# Obstacle_Avoider.net
KiCad netlist of a schematic drawn in EAGLE
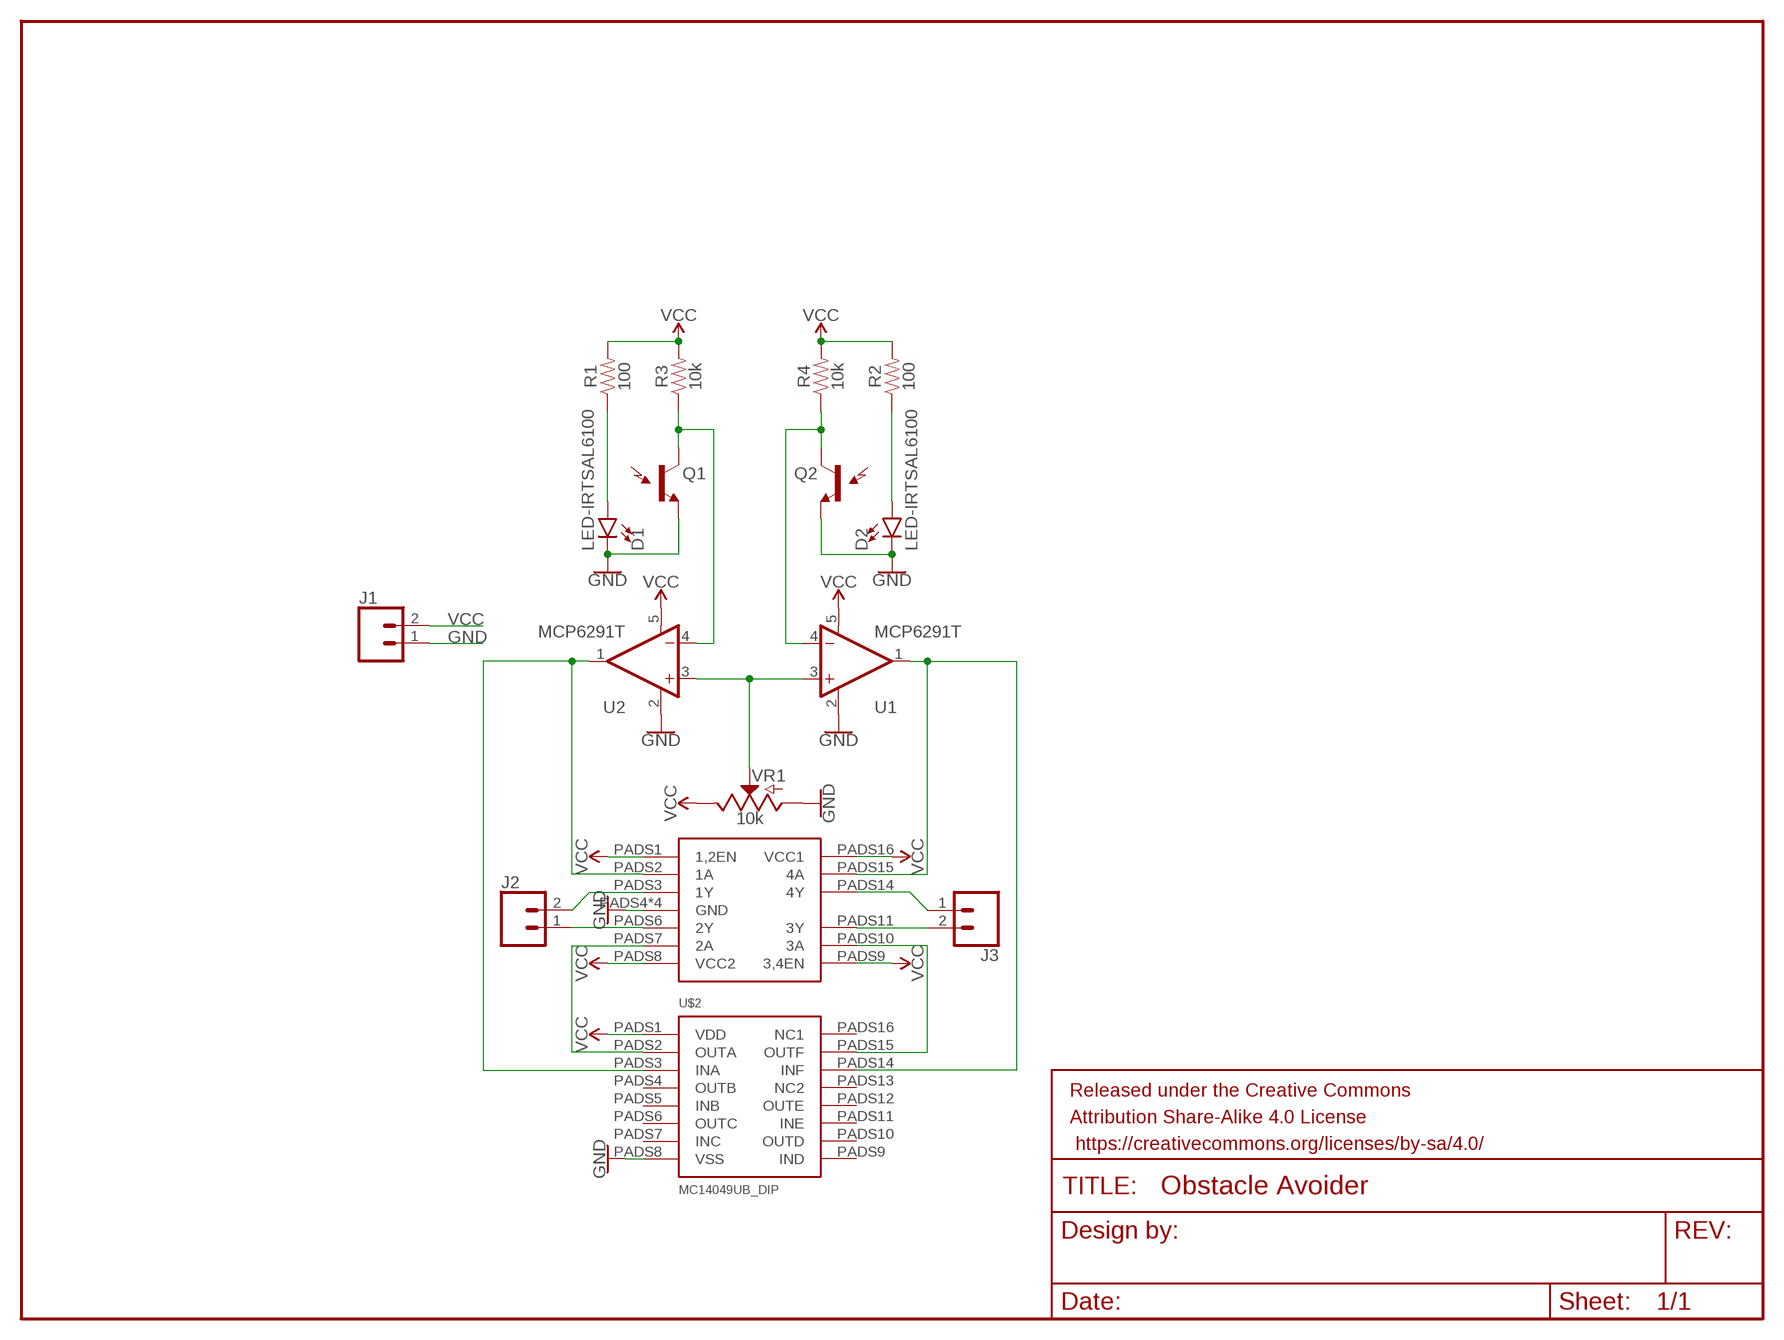
[diagram p0: schematic, sheet 1]

(export (version "E")
  (design (tool "Eeschema 10.0.6"))
  (components
    (comp (ref "D1")
      (value "LED-IRTSAL6100")
      (footprint "eagle-import:LED_5MM")
      (libsource (lib "eagle-import") (part "LED-IRTSAL6100"))
    )
    (comp (ref "D2")
      (value "LED-IRTSAL6100")
      (footprint "eagle-import:LED_5MM")
      (libsource (lib "eagle-import") (part "LED-IRTSAL6100"))
    )
    (comp (ref "FRAME1")
      (value "FRAME-LETTER")
      (footprint "eagle-import:CREATIVE_COMMONS")
      (libsource (lib "eagle-import") (part "FRAME-LETTER"))
    )
    (comp (ref "J1")
      (value "CONN_02")
      (footprint "eagle-import:1X02")
      (libsource (lib "eagle-import") (part "CONN_02"))
    )
    (comp (ref "J2")
      (value "CONN_02")
      (footprint "eagle-import:1X02")
      (libsource (lib "eagle-import") (part "CONN_02"))
    )
    (comp (ref "J3")
      (value "CONN_02")
      (footprint "eagle-import:1X02")
      (libsource (lib "eagle-import") (part "CONN_02"))
    )
    (comp (ref "Q1")
      (value "LTR-301")
      (footprint "eagle-import:LTR-301")
      (libsource (lib "eagle-import") (part "LTR-301"))
    )
    (comp (ref "Q2")
      (value "LTR-301")
      (footprint "eagle-import:LTR-301")
      (libsource (lib "eagle-import") (part "LTR-301"))
    )
    (comp (ref "R1")
      (value "100")
      (footprint "eagle-import:AXIAL-0.3")
      (libsource (lib "eagle-import") (part "100OHM-HORIZ-1/4W-1%"))
    )
    (comp (ref "R2")
      (value "100")
      (footprint "eagle-import:AXIAL-0.3")
      (libsource (lib "eagle-import") (part "100OHM-HORIZ-1/4W-1%"))
    )
    (comp (ref "R3")
      (value "10k")
      (footprint "eagle-import:AXIAL-0.3")
      (libsource (lib "eagle-import") (part "10KOHM-HORIZ-1/4W-1%"))
    )
    (comp (ref "R4")
      (value "10k")
      (footprint "eagle-import:AXIAL-0.3")
      (libsource (lib "eagle-import") (part "10KOHM-HORIZ-1/4W-1%"))
    )
    (comp (ref "U$1")
      (value "L293DNE")
      (footprint "eagle-import:L293DNE")
      (libsource (lib "eagle-import") (part "L293DNE"))
    )
    (comp (ref "U$2")
      (value "MC14049UB_DIP")
      (footprint "eagle-import:MC14049UB_DIP")
      (libsource (lib "eagle-import") (part "MC14049UB_DIP"))
    )
    (comp (ref "U1")
      (value "MCP6291T")
      (footprint "eagle-import:SOT23-5")
      (libsource (lib "eagle-import") (part "MCP6291T-E/OT"))
    )
    (comp (ref "U2")
      (value "MCP6291T")
      (footprint "eagle-import:SOT23-5")
      (libsource (lib "eagle-import") (part "MCP6291T-E/OT"))
    )
    (comp (ref "VR1")
      (value "10k")
      (footprint "eagle-import:POT-PTH-ALPS-KIT")
      (libsource (lib "eagle-import") (part "POTENTIOMETER-PTH-9MM-1/20W-20%-KIT"))
    )
  )
  (nets
    (net (code "1") (name "GND") (class "Default")
      (node (ref "D1") (pin "K") (pinfunction "C_K") (pintype "passive"))
      (node (ref "D2") (pin "K") (pinfunction "C_K") (pintype "passive"))
      (node (ref "J1") (pin "1") (pinfunction "1_1") (pintype "passive"))
      (node (ref "Q1") (pin "E") (pinfunction "E1_E") (pintype "passive"))
      (node (ref "Q2") (pin "E") (pinfunction "E1_E") (pintype "passive"))
      (node (ref "U$1") (pin "PADS12") (pinfunction "GND_PADS12") (pintype "bidirectional"))
      (node (ref "U$1") (pin "PADS13") (pinfunction "GND_PADS13") (pintype "bidirectional"))
      (node (ref "U$1") (pin "PADS4") (pinfunction "GND_PADS4") (pintype "bidirectional"))
      (node (ref "U$1") (pin "PADS5") (pinfunction "GND_PADS5") (pintype "bidirectional"))
      (node (ref "U$2") (pin "PADS8") (pinfunction "VSS_PADS8") (pintype "bidirectional"))
      (node (ref "U1") (pin "2") (pinfunction "V-_2") (pintype "power_in"))
      (node (ref "U2") (pin "2") (pinfunction "V-_2") (pintype "power_in"))
      (node (ref "VR1") (pin "P$3") (pinfunction "A_P$3") (pintype "passive"))
    )
    (net (code "2") (name "Net-(Q1-C1)") (class "Default")
      (node (ref "Q1") (pin "C") (pinfunction "C1_C") (pintype "passive"))
      (node (ref "R3") (pin "P$1") (pinfunction "1_P$1") (pintype "passive"))
      (node (ref "U2") (pin "4") (pinfunction "-IN_4") (pintype "input"))
    )
    (net (code "3") (name "Net-(Q2-C1)") (class "Default")
      (node (ref "Q2") (pin "C") (pinfunction "C1_C") (pintype "passive"))
      (node (ref "R4") (pin "P$1") (pinfunction "1_P$1") (pintype "passive"))
      (node (ref "U1") (pin "4") (pinfunction "-IN_4") (pintype "input"))
    )
    (net (code "4") (name "Net-(R1-1)") (class "Default")
      (node (ref "D1") (pin "A") (pinfunction "A_A") (pintype "passive"))
      (node (ref "R1") (pin "P$1") (pinfunction "1_P$1") (pintype "passive"))
    )
    (net (code "5") (name "Net-(R2-1)") (class "Default")
      (node (ref "D2") (pin "A") (pinfunction "A_A") (pintype "passive"))
      (node (ref "R2") (pin "P$1") (pinfunction "1_P$1") (pintype "passive"))
    )
    (net (code "6") (name "Net-(U$1-1A)") (class "Default")
      (node (ref "U$1") (pin "PADS2") (pinfunction "1A_PADS2") (pintype "bidirectional"))
      (node (ref "U$2") (pin "PADS3") (pinfunction "INA_PADS3") (pintype "bidirectional"))
      (node (ref "U2") (pin "1") (pinfunction "OUT_1") (pintype "output"))
    )
    (net (code "7") (name "Net-(U$1-1Y)") (class "Default")
      (node (ref "J2") (pin "2") (pinfunction "2_2") (pintype "passive"))
      (node (ref "U$1") (pin "PADS3") (pinfunction "1Y_PADS3") (pintype "bidirectional"))
    )
    (net (code "8") (name "Net-(U$1-2A)") (class "Default")
      (node (ref "U$1") (pin "PADS7") (pinfunction "2A_PADS7") (pintype "bidirectional"))
      (node (ref "U$2") (pin "PADS2") (pinfunction "OUTA_PADS2") (pintype "bidirectional"))
    )
    (net (code "9") (name "Net-(U$1-2Y)") (class "Default")
      (node (ref "J2") (pin "1") (pinfunction "1_1") (pintype "passive"))
      (node (ref "U$1") (pin "PADS6") (pinfunction "2Y_PADS6") (pintype "bidirectional"))
    )
    (net (code "10") (name "Net-(U$1-3A)") (class "Default")
      (node (ref "U$1") (pin "PADS10") (pinfunction "3A_PADS10") (pintype "bidirectional"))
      (node (ref "U$2") (pin "PADS15") (pinfunction "OUTF_PADS15") (pintype "bidirectional"))
    )
    (net (code "11") (name "Net-(U$1-3Y)") (class "Default")
      (node (ref "J3") (pin "2") (pinfunction "2_2") (pintype "passive"))
      (node (ref "U$1") (pin "PADS11") (pinfunction "3Y_PADS11") (pintype "bidirectional"))
    )
    (net (code "12") (name "Net-(U$1-4A)") (class "Default")
      (node (ref "U$1") (pin "PADS15") (pinfunction "4A_PADS15") (pintype "bidirectional"))
      (node (ref "U$2") (pin "PADS14") (pinfunction "INF_PADS14") (pintype "bidirectional"))
      (node (ref "U1") (pin "1") (pinfunction "OUT_1") (pintype "output"))
    )
    (net (code "13") (name "Net-(U$1-4Y)") (class "Default")
      (node (ref "J3") (pin "1") (pinfunction "1_1") (pintype "passive"))
      (node (ref "U$1") (pin "PADS14") (pinfunction "4Y_PADS14") (pintype "bidirectional"))
    )
    (net (code "14") (name "Net-(U1-+IN)") (class "Default")
      (node (ref "U1") (pin "3") (pinfunction "+IN_3") (pintype "input"))
      (node (ref "U2") (pin "3") (pinfunction "+IN_3") (pintype "input"))
      (node (ref "VR1") (pin "P$2") (pinfunction "S_P$2") (pintype "passive"))
    )
    (net (code "15") (name "VCC") (class "Default")
      (node (ref "J1") (pin "2") (pinfunction "2_2") (pintype "passive"))
      (node (ref "R1") (pin "P$2") (pinfunction "2_P$2") (pintype "passive"))
      (node (ref "R2") (pin "P$2") (pinfunction "2_P$2") (pintype "passive"))
      (node (ref "R3") (pin "P$2") (pinfunction "2_P$2") (pintype "passive"))
      (node (ref "R4") (pin "P$2") (pinfunction "2_P$2") (pintype "passive"))
      (node (ref "U$1") (pin "PADS1") (pinfunction "1,2EN_PADS1") (pintype "bidirectional"))
      (node (ref "U$1") (pin "PADS16") (pinfunction "VCC1_PADS16") (pintype "bidirectional"))
      (node (ref "U$1") (pin "PADS8") (pinfunction "VCC2_PADS8") (pintype "bidirectional"))
      (node (ref "U$1") (pin "PADS9") (pinfunction "3,4EN_PADS9") (pintype "bidirectional"))
      (node (ref "U$2") (pin "PADS1") (pinfunction "VDD_PADS1") (pintype "bidirectional"))
      (node (ref "U1") (pin "5") (pinfunction "V+_5") (pintype "power_in"))
      (node (ref "U2") (pin "5") (pinfunction "V+_5") (pintype "power_in"))
      (node (ref "VR1") (pin "P$1") (pinfunction "E_P$1") (pintype "passive"))
    )
    (net (code "16") (name "unconnected-(U$2-INB-PadPADS5)") (class "Default")
      (node (ref "U$2") (pin "PADS5") (pinfunction "INB_PADS5") (pintype "bidirectional"))
    )
    (net (code "17") (name "unconnected-(U$2-INC-PadPADS7)") (class "Default")
      (node (ref "U$2") (pin "PADS7") (pinfunction "INC_PADS7") (pintype "bidirectional"))
    )
    (net (code "18") (name "unconnected-(U$2-IND-PadPADS9)") (class "Default")
      (node (ref "U$2") (pin "PADS9") (pinfunction "IND_PADS9") (pintype "bidirectional"))
    )
    (net (code "19") (name "unconnected-(U$2-INE-PadPADS11)") (class "Default")
      (node (ref "U$2") (pin "PADS11") (pinfunction "INE_PADS11") (pintype "bidirectional"))
    )
    (net (code "20") (name "unconnected-(U$2-NC1-PadPADS16)") (class "Default")
      (node (ref "U$2") (pin "PADS16") (pinfunction "NC1_PADS16") (pintype "bidirectional"))
    )
    (net (code "21") (name "unconnected-(U$2-NC2-PadPADS13)") (class "Default")
      (node (ref "U$2") (pin "PADS13") (pinfunction "NC2_PADS13") (pintype "bidirectional"))
    )
    (net (code "22") (name "unconnected-(U$2-OUTB-PadPADS4)") (class "Default")
      (node (ref "U$2") (pin "PADS4") (pinfunction "OUTB_PADS4") (pintype "bidirectional"))
    )
    (net (code "23") (name "unconnected-(U$2-OUTC-PadPADS6)") (class "Default")
      (node (ref "U$2") (pin "PADS6") (pinfunction "OUTC_PADS6") (pintype "bidirectional"))
    )
    (net (code "24") (name "unconnected-(U$2-OUTD-PadPADS10)") (class "Default")
      (node (ref "U$2") (pin "PADS10") (pinfunction "OUTD_PADS10") (pintype "bidirectional"))
    )
    (net (code "25") (name "unconnected-(U$2-OUTE-PadPADS12)") (class "Default")
      (node (ref "U$2") (pin "PADS12") (pinfunction "OUTE_PADS12") (pintype "bidirectional"))
    )
  )
)
